# MQTT_Monitor_v2.net
KiCad netlist of a schematic drawn in EAGLE
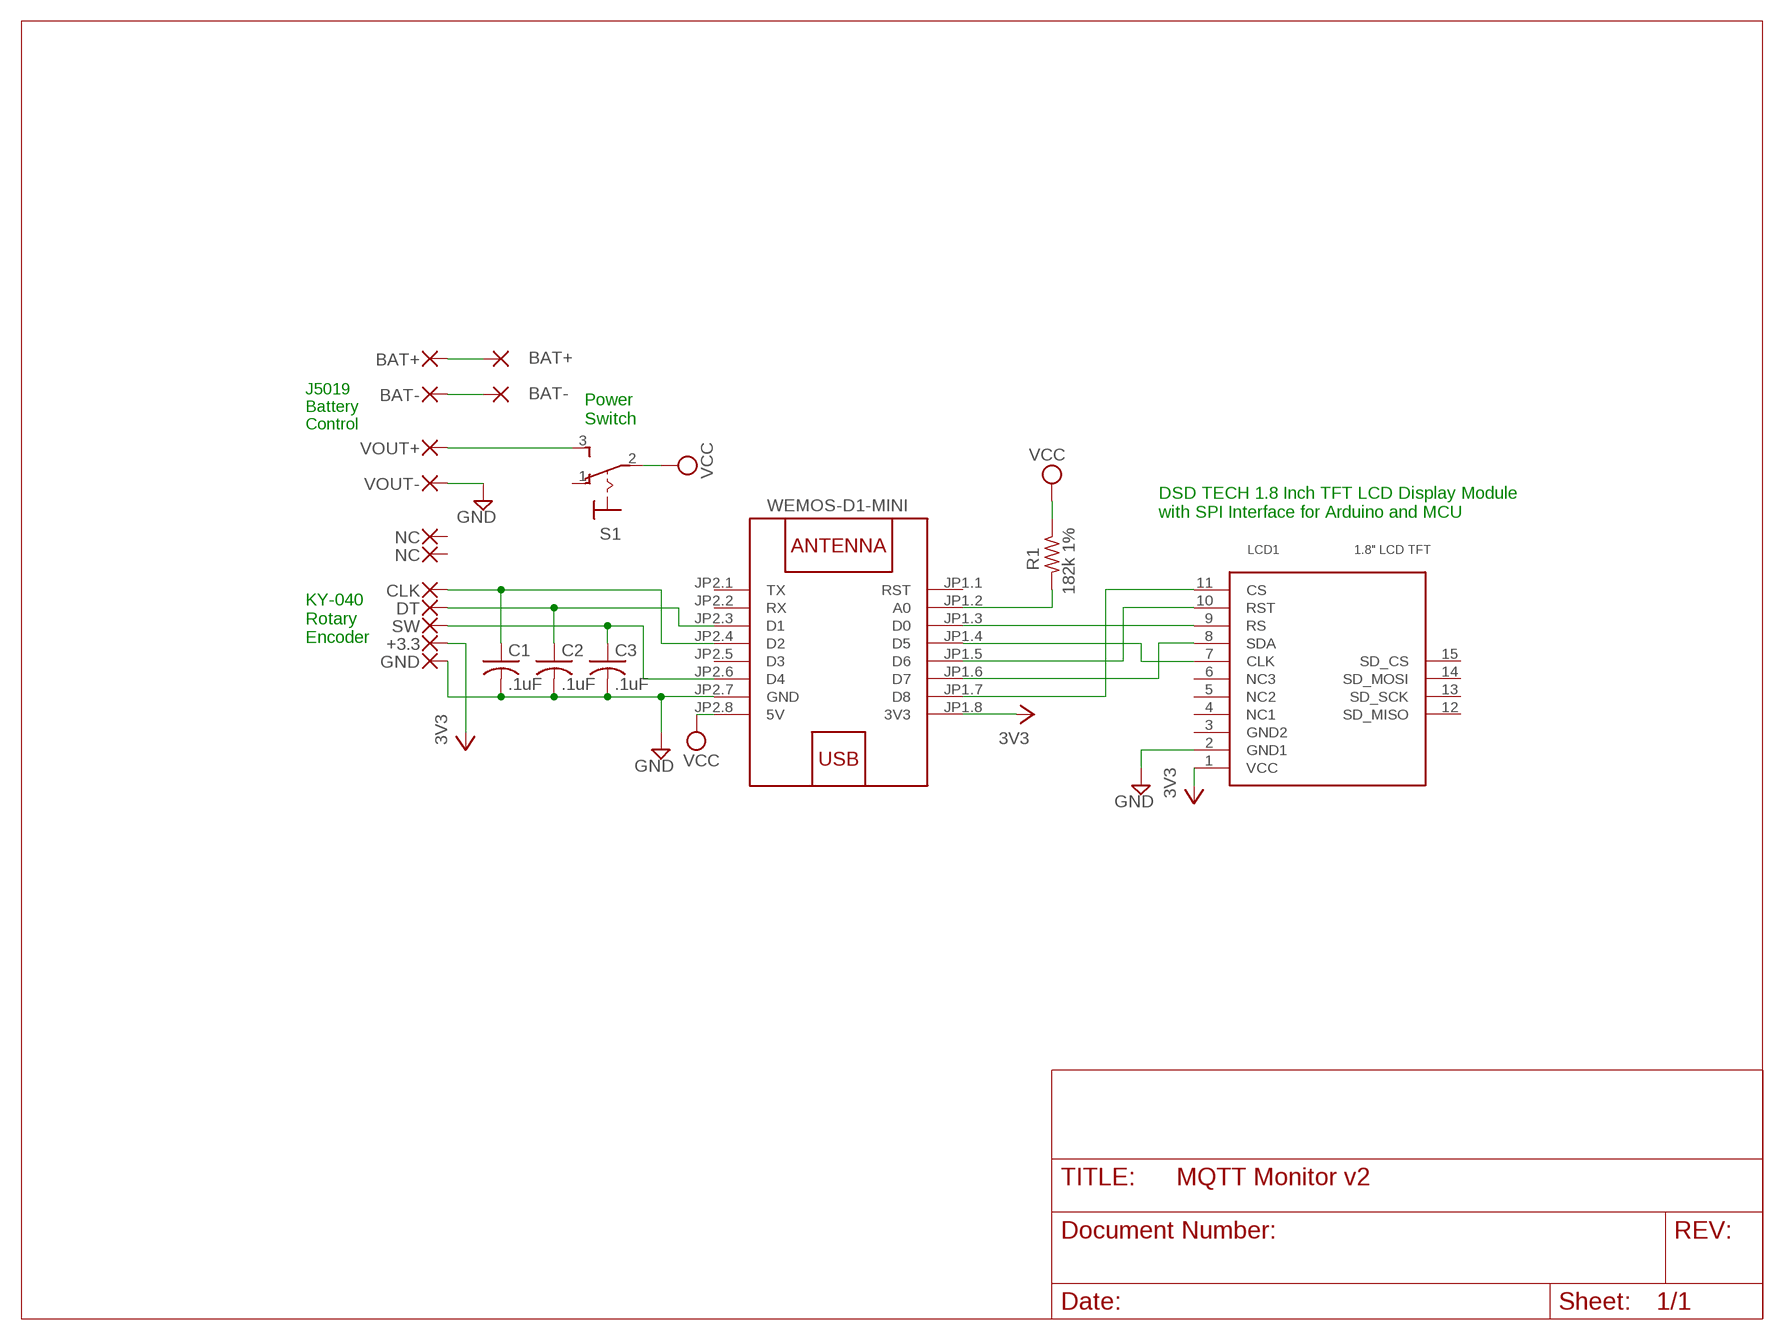
[diagram p0: schematic, sheet 1]

(export (version "E")
  (design (tool "Eeschema 10.0.6"))
  (components
    (comp (ref "C1")
      (value ".1uF")
      (footprint "eagle-import:C1206")
      (libsource (lib "eagle-import") (part "C-USC1206"))
    )
    (comp (ref "C2")
      (value ".1uF")
      (footprint "eagle-import:C1206")
      (libsource (lib "eagle-import") (part "C-USC1206"))
    )
    (comp (ref "C3")
      (value ".1uF")
      (footprint "eagle-import:C1206")
      (libsource (lib "eagle-import") (part "C-USC1206"))
    )
    (comp (ref "LCD1")
      (value "1.8\" LCD TFT")
      (footprint "eagle-import:DSDTECH1.8_TFT")
      (libsource (lib "eagle-import") (part "DSDTECH1.8{dblquote}TFT"))
    )
    (comp (ref "PAD1")
      (value "CLK")
      (footprint "eagle-import:2,15_1,0")
      (libsource (lib "eagle-import") (part "2,15/1,0"))
    )
    (comp (ref "PAD2")
      (value "DT")
      (footprint "eagle-import:2,15_1,0")
      (libsource (lib "eagle-import") (part "2,15/1,0"))
    )
    (comp (ref "PAD3")
      (value "SW")
      (footprint "eagle-import:2,15_1,0")
      (libsource (lib "eagle-import") (part "2,15/1,0"))
    )
    (comp (ref "PAD4")
      (value "+3.3")
      (footprint "eagle-import:2,15_1,0")
      (libsource (lib "eagle-import") (part "2,15/1,0"))
    )
    (comp (ref "PAD5")
      (value "GND")
      (footprint "eagle-import:2,15_1,0")
      (libsource (lib "eagle-import") (part "2,15/1,0"))
    )
    (comp (ref "PAD6")
      (value "VOUT+")
      (footprint "eagle-import:2,15_1,0")
      (libsource (lib "eagle-import") (part "2,15/1,0"))
    )
    (comp (ref "PAD7")
      (value "VOUT-")
      (footprint "eagle-import:2,15_1,0")
      (libsource (lib "eagle-import") (part "2,15/1,0"))
    )
    (comp (ref "PAD8")
      (value "BAT+")
      (footprint "eagle-import:2,15_1,0")
      (libsource (lib "eagle-import") (part "2,15/1,0"))
    )
    (comp (ref "PAD9")
      (value "BAT-")
      (footprint "eagle-import:2,15_1,0")
      (libsource (lib "eagle-import") (part "2,15/1,0"))
    )
    (comp (ref "PAD10")
      (value "BAT+")
      (footprint "eagle-import:2,15_1,0")
      (libsource (lib "eagle-import") (part "2,15/1,0"))
    )
    (comp (ref "PAD11")
      (value "BAT-")
      (footprint "eagle-import:2,15_1,0")
      (libsource (lib "eagle-import") (part "2,15/1,0"))
    )
    (comp (ref "PAD12")
      (value "NC")
      (footprint "eagle-import:2,15_1,0")
      (libsource (lib "eagle-import") (part "2,15/1,0"))
    )
    (comp (ref "PAD13")
      (value "NC")
      (footprint "eagle-import:2,15_1,0")
      (libsource (lib "eagle-import") (part "2,15/1,0"))
    )
    (comp (ref "R1")
      (value "182k 1%")
      (footprint "eagle-import:R1206")
      (libsource (lib "eagle-import") (part "R-US_R1206"))
    )
    (comp (ref "S1")
      (value "320-916")
      (footprint "eagle-import:320-916")
      (libsource (lib "eagle-import") (part "320-916"))
    )
    (comp (ref "U$1")
      (value "WEMOS-D1-MINI")
      (footprint "eagle-import:WEMOS-D1-MINI")
      (libsource (lib "eagle-import") (part "WEMOS-D1-MINI"))
    )
  )
  (nets
    (net (code "1") (name "3V3") (class "Default")
      (node (ref "LCD1") (pin "1") (pinfunction "VCC_1") (pintype "bidirectional"))
      (node (ref "PAD4") (pin "1") (pinfunction "P_1") (pintype "passive"))
      (node (ref "U$1") (pin "JP1.8") (pinfunction "3V3_JP1.8") (pintype "power_in"))
    )
    (net (code "2") (name "GND") (class "Default")
      (node (ref "C1") (pin "2") (pinfunction "2_2") (pintype "passive"))
      (node (ref "C2") (pin "2") (pinfunction "2_2") (pintype "passive"))
      (node (ref "C3") (pin "2") (pinfunction "2_2") (pintype "passive"))
      (node (ref "LCD1") (pin "2") (pinfunction "GND1_2") (pintype "bidirectional"))
      (node (ref "PAD5") (pin "1") (pinfunction "P_1") (pintype "passive"))
      (node (ref "PAD7") (pin "1") (pinfunction "P_1") (pintype "passive"))
      (node (ref "U$1") (pin "JP2.7") (pinfunction "GND_JP2.7") (pintype "power_in"))
    )
    (net (code "3") (name "Net-(LCD1-CLK)") (class "Default")
      (node (ref "LCD1") (pin "7") (pinfunction "CLK_7") (pintype "bidirectional"))
      (node (ref "U$1") (pin "JP1.4") (pinfunction "D5_JP1.4") (pintype "bidirectional"))
    )
    (net (code "4") (name "Net-(LCD1-CS)") (class "Default")
      (node (ref "LCD1") (pin "11") (pinfunction "CS_11") (pintype "bidirectional"))
      (node (ref "U$1") (pin "JP1.7") (pinfunction "D8_JP1.7") (pintype "bidirectional"))
    )
    (net (code "5") (name "Net-(LCD1-RS)") (class "Default")
      (node (ref "LCD1") (pin "9") (pinfunction "RS_9") (pintype "bidirectional"))
      (node (ref "U$1") (pin "JP1.3") (pinfunction "D0_JP1.3") (pintype "bidirectional"))
    )
    (net (code "6") (name "Net-(LCD1-RST)") (class "Default")
      (node (ref "LCD1") (pin "10") (pinfunction "RST_10") (pintype "bidirectional"))
      (node (ref "U$1") (pin "JP1.5") (pinfunction "D6_JP1.5") (pintype "bidirectional"))
    )
    (net (code "7") (name "Net-(LCD1-SDA)") (class "Default")
      (node (ref "LCD1") (pin "8") (pinfunction "SDA_8") (pintype "bidirectional"))
      (node (ref "U$1") (pin "JP1.6") (pinfunction "D7_JP1.6") (pintype "bidirectional"))
    )
    (net (code "8") (name "Net-(PAD1-P)") (class "Default")
      (node (ref "C1") (pin "1") (pinfunction "1_1") (pintype "passive"))
      (node (ref "PAD1") (pin "1") (pinfunction "P_1") (pintype "passive"))
      (node (ref "U$1") (pin "JP2.4") (pinfunction "D2_JP2.4") (pintype "bidirectional"))
    )
    (net (code "9") (name "Net-(PAD2-P)") (class "Default")
      (node (ref "C2") (pin "1") (pinfunction "1_1") (pintype "passive"))
      (node (ref "PAD2") (pin "1") (pinfunction "P_1") (pintype "passive"))
      (node (ref "U$1") (pin "JP2.3") (pinfunction "D1_JP2.3") (pintype "bidirectional"))
    )
    (net (code "10") (name "Net-(PAD3-P)") (class "Default")
      (node (ref "C3") (pin "1") (pinfunction "1_1") (pintype "passive"))
      (node (ref "PAD3") (pin "1") (pinfunction "P_1") (pintype "passive"))
      (node (ref "U$1") (pin "JP2.6") (pinfunction "D4_JP2.6") (pintype "bidirectional"))
    )
    (net (code "11") (name "Net-(PAD6-P)") (class "Default")
      (node (ref "PAD6") (pin "1") (pinfunction "P_1") (pintype "passive"))
      (node (ref "S1") (pin "3") (pinfunction "S_3") (pintype "passive"))
    )
    (net (code "12") (name "Net-(PAD10-P)") (class "Default")
      (node (ref "PAD10") (pin "1") (pinfunction "P_1") (pintype "passive"))
      (node (ref "PAD8") (pin "1") (pinfunction "P_1") (pintype "passive"))
    )
    (net (code "13") (name "Net-(PAD11-P)") (class "Default")
      (node (ref "PAD11") (pin "1") (pinfunction "P_1") (pintype "passive"))
      (node (ref "PAD9") (pin "1") (pinfunction "P_1") (pintype "passive"))
    )
    (net (code "14") (name "Net-(U$1-A0)") (class "Default")
      (node (ref "R1") (pin "2") (pinfunction "2_2") (pintype "passive"))
      (node (ref "U$1") (pin "JP1.2") (pinfunction "A0_JP1.2") (pintype "bidirectional"))
    )
    (net (code "15") (name "VCC") (class "Default")
      (node (ref "R1") (pin "1") (pinfunction "1_1") (pintype "passive"))
      (node (ref "S1") (pin "2") (pinfunction "P_2") (pintype "passive"))
      (node (ref "U$1") (pin "JP2.8") (pinfunction "5V_JP2.8") (pintype "power_in"))
    )
    (net (code "16") (name "unconnected-(LCD1-GND2-Pad3)") (class "Default")
      (node (ref "LCD1") (pin "3") (pinfunction "GND2_3") (pintype "bidirectional"))
    )
    (net (code "17") (name "unconnected-(LCD1-NC1-Pad4)") (class "Default")
      (node (ref "LCD1") (pin "4") (pinfunction "NC1_4") (pintype "bidirectional"))
    )
    (net (code "18") (name "unconnected-(LCD1-NC2-Pad5)") (class "Default")
      (node (ref "LCD1") (pin "5") (pinfunction "NC2_5") (pintype "bidirectional"))
    )
    (net (code "19") (name "unconnected-(LCD1-NC3-Pad6)") (class "Default")
      (node (ref "LCD1") (pin "6") (pinfunction "NC3_6") (pintype "bidirectional"))
    )
    (net (code "20") (name "unconnected-(LCD1-SD_CS-Pad15)") (class "Default")
      (node (ref "LCD1") (pin "15") (pinfunction "SD_CS_15") (pintype "bidirectional"))
    )
    (net (code "21") (name "unconnected-(LCD1-SD_MISO-Pad12)") (class "Default")
      (node (ref "LCD1") (pin "12") (pinfunction "SD_MISO_12") (pintype "bidirectional"))
    )
    (net (code "22") (name "unconnected-(LCD1-SD_MOSI-Pad14)") (class "Default")
      (node (ref "LCD1") (pin "14") (pinfunction "SD_MOSI_14") (pintype "bidirectional"))
    )
    (net (code "23") (name "unconnected-(LCD1-SD_SCK-Pad13)") (class "Default")
      (node (ref "LCD1") (pin "13") (pinfunction "SD_SCK_13") (pintype "bidirectional"))
    )
    (net (code "24") (name "unconnected-(PAD12-P-Pad1)") (class "Default")
      (node (ref "PAD12") (pin "1") (pinfunction "P_1") (pintype "passive"))
    )
    (net (code "25") (name "unconnected-(PAD13-P-Pad1)") (class "Default")
      (node (ref "PAD13") (pin "1") (pinfunction "P_1") (pintype "passive"))
    )
    (net (code "26") (name "unconnected-(S1-O-Pad1)") (class "Default")
      (node (ref "S1") (pin "1") (pinfunction "O_1") (pintype "passive"))
    )
    (net (code "27") (name "unconnected-(U$1-D3-PadJP2.5)") (class "Default")
      (node (ref "U$1") (pin "JP2.5") (pinfunction "D3_JP2.5") (pintype "bidirectional"))
    )
    (net (code "28") (name "unconnected-(U$1-RST-PadJP1.1)") (class "Default")
      (node (ref "U$1") (pin "JP1.1") (pinfunction "RST_JP1.1") (pintype "bidirectional"))
    )
    (net (code "29") (name "unconnected-(U$1-RX-PadJP2.2)") (class "Default")
      (node (ref "U$1") (pin "JP2.2") (pinfunction "RX_JP2.2") (pintype "bidirectional"))
    )
    (net (code "30") (name "unconnected-(U$1-TX-PadJP2.1)") (class "Default")
      (node (ref "U$1") (pin "JP2.1") (pinfunction "TX_JP2.1") (pintype "bidirectional"))
    )
  )
)
